# Helmet_Drop_V1.net
KiCad netlist of a schematic drawn in EAGLE
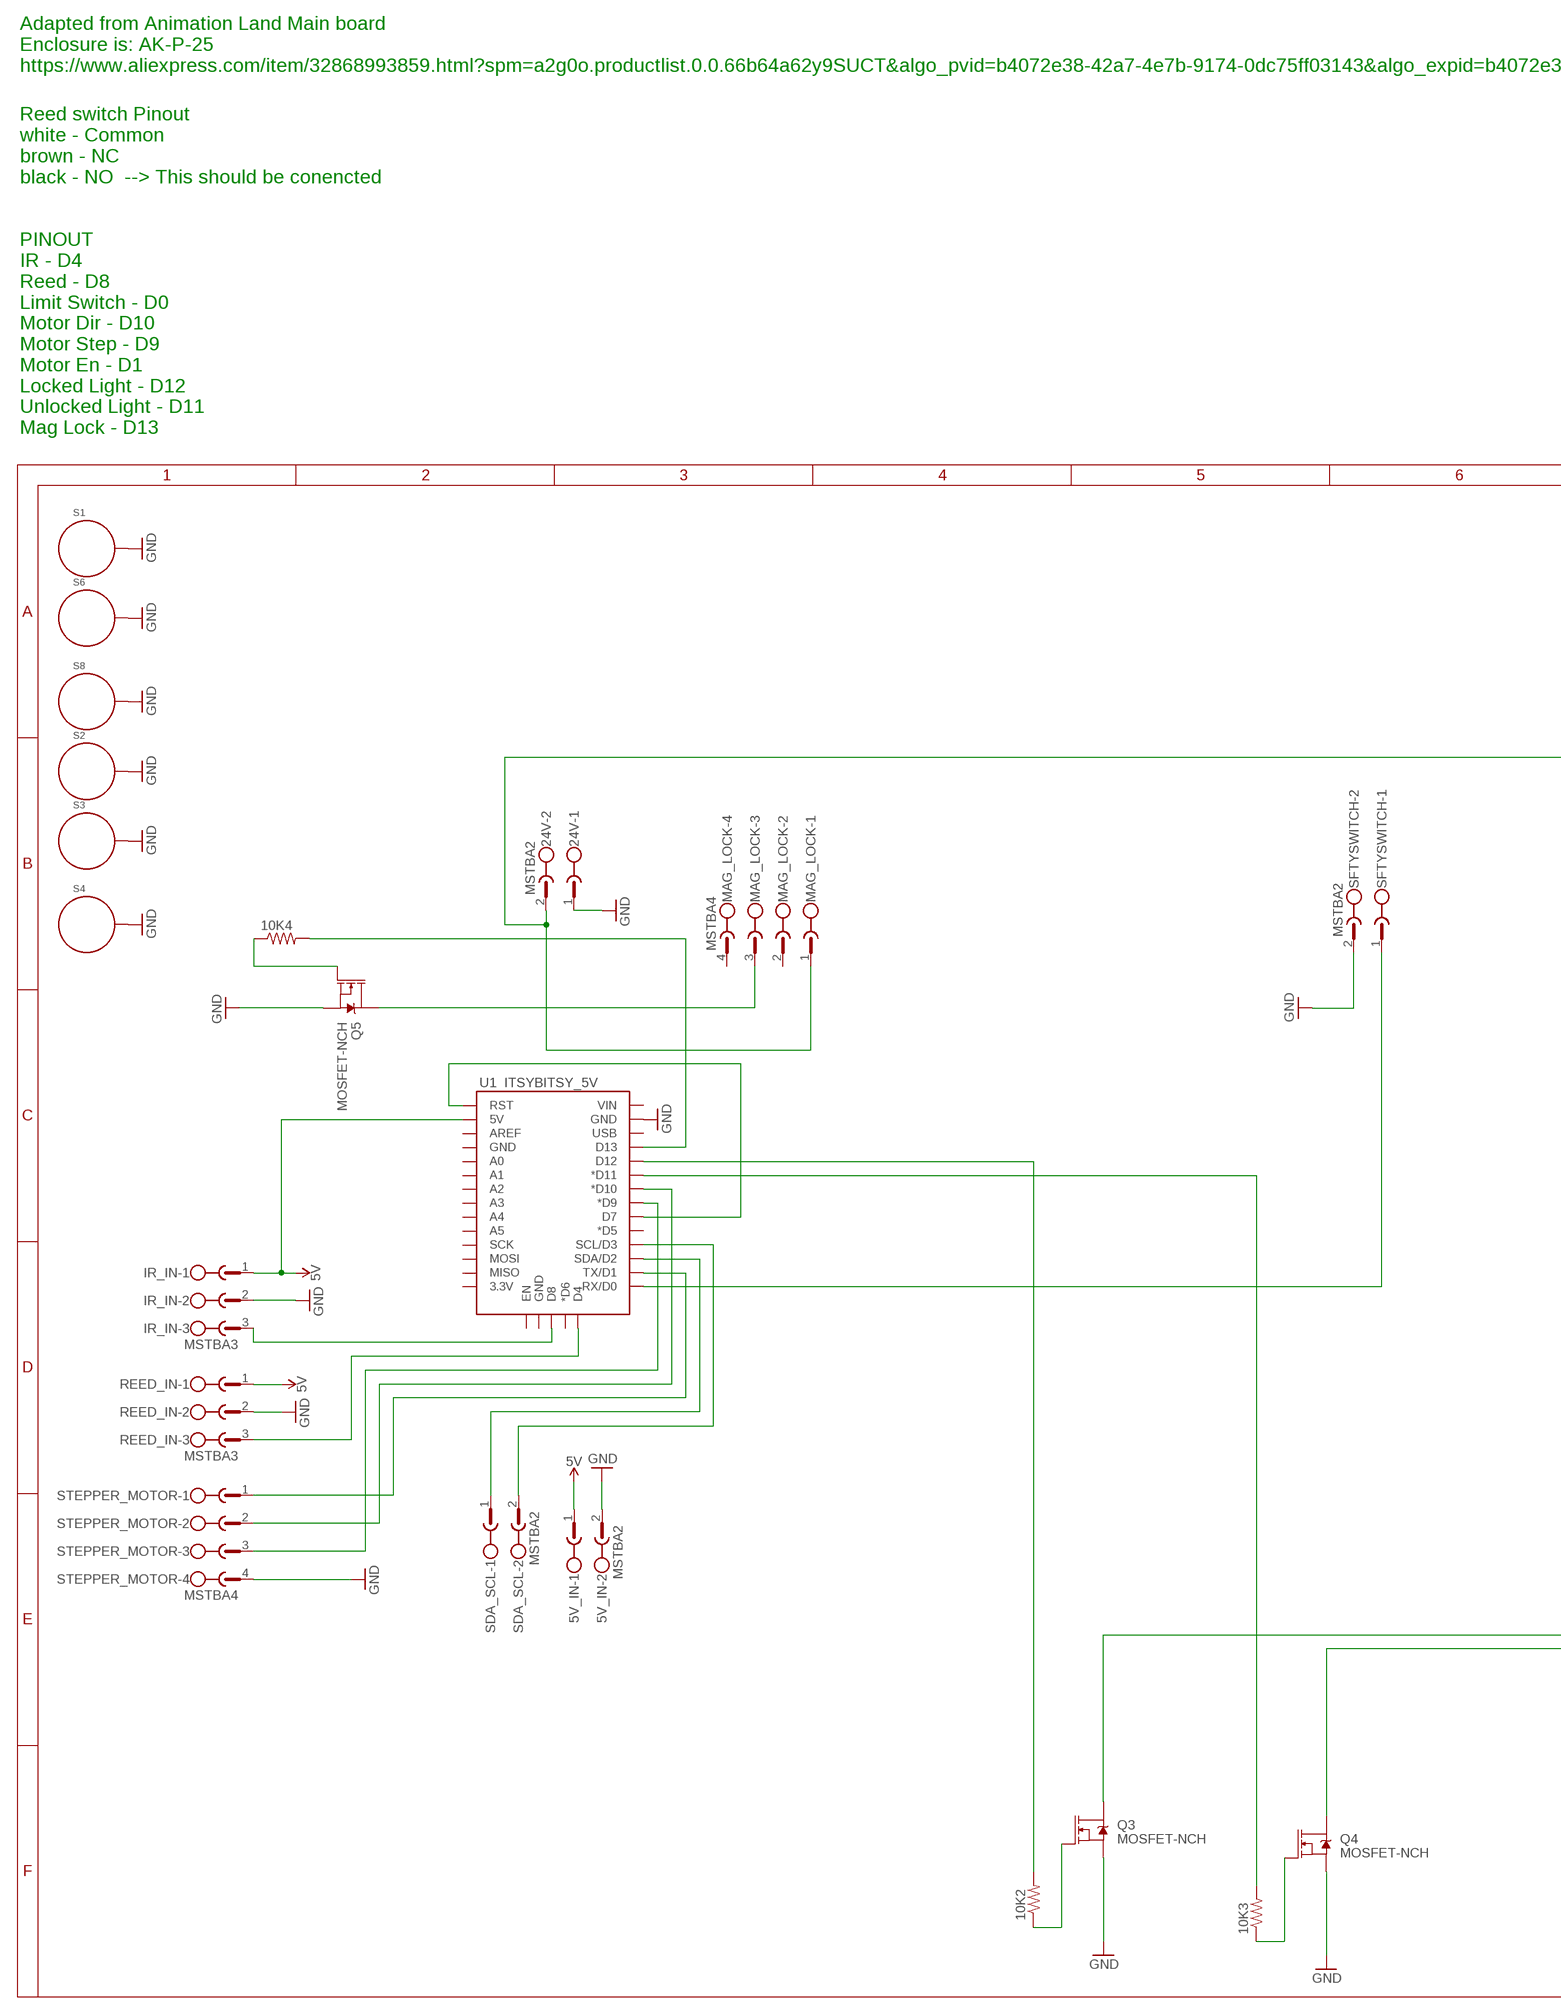
[diagram p0: schematic, sheet 1, part 1 of 2]
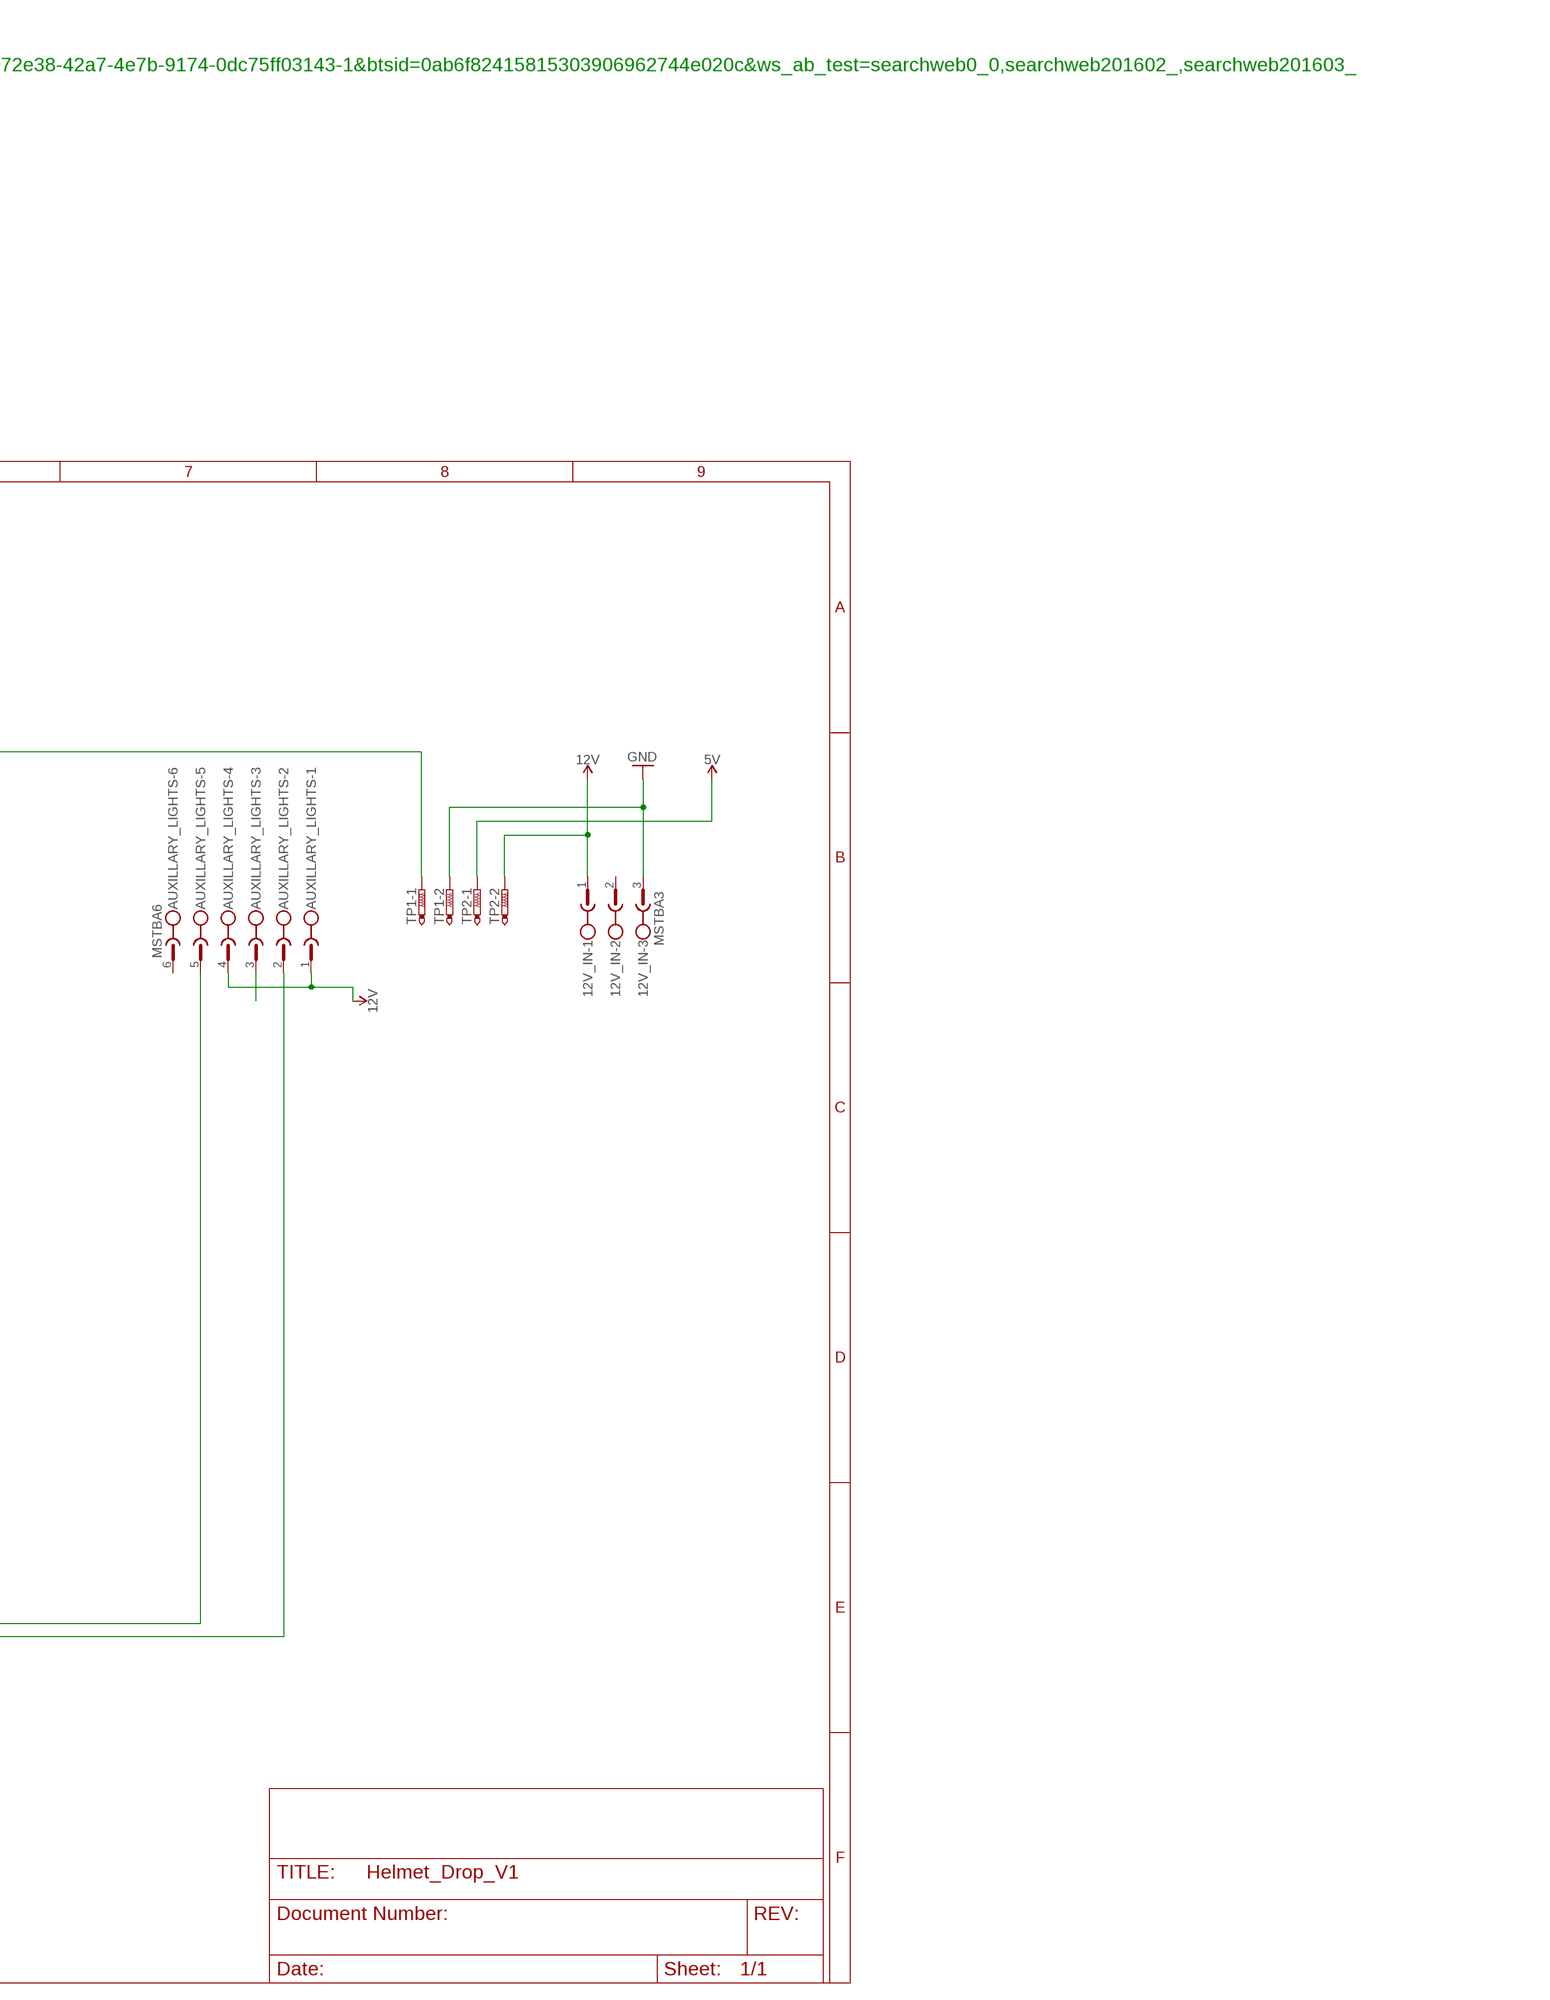
[diagram p1: schematic, sheet 1, part 2 of 2]

(export (version "E")
  (design (tool "Eeschema 10.0.6"))
  (components
    (comp (ref "5V_IN")
      (value "MSTBA2")
      (footprint "eagle-import:MSTBA2")
      (fields (field (name "MF") "FARNELL") (field (name "MPN") "1757242"))
      (libsource (lib "eagle-import") (part "MSTBA2"))
    )
    (comp (ref "10K2")
      (value "R-US_M0805")
      (footprint "eagle-import:M0805")
      (libsource (lib "eagle-import") (part "R-US_M0805"))
    )
    (comp (ref "10K3")
      (value "R-US_M0805")
      (footprint "eagle-import:M0805")
      (libsource (lib "eagle-import") (part "R-US_M0805"))
    )
    (comp (ref "10K4")
      (value "R-US_M0805")
      (footprint "eagle-import:M0805")
      (libsource (lib "eagle-import") (part "R-US_M0805"))
    )
    (comp (ref "12V_IN")
      (value "MSTBA3")
      (footprint "eagle-import:MSTBA3")
      (fields (field (name "MF") "FARNELL") (field (name "MPN") "1757255"))
      (libsource (lib "eagle-import") (part "MSTBA3"))
    )
    (comp (ref "24V")
      (value "MSTBA2")
      (footprint "eagle-import:MSTBA2")
      (fields (field (name "MF") "FARNELL") (field (name "MPN") "1757242"))
      (libsource (lib "eagle-import") (part "MSTBA2"))
    )
    (comp (ref "AUXILLARY_LIGHTS")
      (value "MSTBA6")
      (footprint "eagle-import:MSTBA6")
      (fields (field (name "MF") "FARNELL") (field (name "MPN") "1757284"))
      (libsource (lib "eagle-import") (part "MSTBA6"))
    )
    (comp (ref "IR_IN")
      (value "MSTBA3")
      (footprint "eagle-import:MSTBA3")
      (fields (field (name "MF") "FARNELL") (field (name "MPN") "1757255"))
      (libsource (lib "eagle-import") (part "MSTBA3"))
    )
    (comp (ref "MAG_LOCK")
      (value "MSTBA4")
      (footprint "eagle-import:MSTBA4")
      (fields (field (name "MF") "FARNELL") (field (name "MPN") "1757268"))
      (libsource (lib "eagle-import") (part "MSTBA4"))
    )
    (comp (ref "Q3")
      (value "MOSFET-NCH")
      (footprint "eagle-import:SO-8_POWER_PAK")
      (libsource (lib "eagle-import") (part "MOSFET-NCH"))
    )
    (comp (ref "Q4")
      (value "MOSFET-NCH")
      (footprint "eagle-import:SO-8_POWER_PAK")
      (libsource (lib "eagle-import") (part "MOSFET-NCH"))
    )
    (comp (ref "Q5")
      (value "MOSFET-NCH")
      (footprint "eagle-import:SO-8_POWER_PAK")
      (libsource (lib "eagle-import") (part "MOSFET-NCH"))
    )
    (comp (ref "REED_IN")
      (value "MSTBA3")
      (footprint "eagle-import:MSTBA3")
      (fields (field (name "MF") "FARNELL") (field (name "MPN") "1757255"))
      (libsource (lib "eagle-import") (part "MSTBA3"))
    )
    (comp (ref "S1")
      (value "STANDOFF_ELECTRICAL5-32")
      (footprint "eagle-import:STANDOFF_ELECTRICAL_5_32")
      (libsource (lib "eagle-import") (part "STANDOFF_ELECTRICAL5-32"))
    )
    (comp (ref "S2")
      (value "STANDOFF_ELECTRICAL5-32")
      (footprint "eagle-import:STANDOFF_ELECTRICAL_5_32")
      (libsource (lib "eagle-import") (part "STANDOFF_ELECTRICAL5-32"))
    )
    (comp (ref "S3")
      (value "STANDOFF_ELECTRICAL5-32")
      (footprint "eagle-import:STANDOFF_ELECTRICAL_5_32")
      (libsource (lib "eagle-import") (part "STANDOFF_ELECTRICAL5-32"))
    )
    (comp (ref "S4")
      (value "STANDOFF_ELECTRICAL5-32")
      (footprint "eagle-import:STANDOFF_ELECTRICAL_5_32")
      (libsource (lib "eagle-import") (part "STANDOFF_ELECTRICAL5-32"))
    )
    (comp (ref "S6")
      (value "STANDOFF_ELECTRICAL5-32")
      (footprint "eagle-import:STANDOFF_ELECTRICAL_5_32")
      (libsource (lib "eagle-import") (part "STANDOFF_ELECTRICAL5-32"))
    )
    (comp (ref "S8")
      (value "STANDOFF_ELECTRICAL5-32")
      (footprint "eagle-import:STANDOFF_ELECTRICAL_5_32")
      (libsource (lib "eagle-import") (part "STANDOFF_ELECTRICAL5-32"))
    )
    (comp (ref "SDA_SCL")
      (value "MSTBA2")
      (footprint "eagle-import:MSTBA2")
      (fields (field (name "MF") "FARNELL") (field (name "MPN") "1757242"))
      (libsource (lib "eagle-import") (part "MSTBA2"))
    )
    (comp (ref "SFTYSWITCH")
      (value "MSTBA2")
      (footprint "eagle-import:MSTBA2")
      (fields (field (name "MF") "FARNELL") (field (name "MPN") "1757242"))
      (libsource (lib "eagle-import") (part "MSTBA2"))
    )
    (comp (ref "STEPPER_MOTOR")
      (value "MSTBA4")
      (footprint "eagle-import:MSTBA4")
      (fields (field (name "MF") "FARNELL") (field (name "MPN") "1757268"))
      (libsource (lib "eagle-import") (part "MSTBA4"))
    )
    (comp (ref "TP1")
      (value "PTR2")
      (footprint "eagle-import:P2-38-17")
      (libsource (lib "eagle-import") (part "PTR2"))
    )
    (comp (ref "TP2")
      (value "PTR2")
      (footprint "eagle-import:P2-38-17")
      (libsource (lib "eagle-import") (part "PTR2"))
    )
    (comp (ref "U1")
      (value "ITSYBITSY_5V")
      (footprint "eagle-import:ADAFRUIT_LENOARDO")
      (libsource (lib "eagle-import") (part "ITSYBITSY_5V"))
    )
  )
  (nets
    (net (code "1") (name "5V") (class "Default")
      (node (ref "5V_IN") (pin "1") (pinfunction "1_1") (pintype "passive"))
      (node (ref "IR_IN") (pin "1") (pinfunction "1_1") (pintype "passive"))
      (node (ref "REED_IN") (pin "1") (pinfunction "1_1") (pintype "passive"))
      (node (ref "TP2") (pin "TP-1") (pinfunction "TP_TP-1") (pintype "input"))
      (node (ref "U1") (pin "5V") (pinfunction "5V_5V") (pintype "bidirectional"))
    )
    (net (code "2") (name "12V") (class "Default")
      (node (ref "12V_IN") (pin "1") (pinfunction "1_1") (pintype "passive"))
      (node (ref "AUXILLARY_LIGHTS") (pin "1") (pinfunction "1_1") (pintype "passive"))
      (node (ref "AUXILLARY_LIGHTS") (pin "4") (pinfunction "1_4") (pintype "passive"))
      (node (ref "TP2") (pin "TP-2") (pinfunction "TP_TP-2") (pintype "input"))
    )
    (net (code "3") (name "GND") (class "Default")
      (node (ref "12V_IN") (pin "3") (pinfunction "1_3") (pintype "passive"))
      (node (ref "24V") (pin "1") (pinfunction "1_1") (pintype "passive"))
      (node (ref "5V_IN") (pin "2") (pinfunction "1_2") (pintype "passive"))
      (node (ref "IR_IN") (pin "2") (pinfunction "1_2") (pintype "passive"))
      (node (ref "Q3") (pin "S") (pinfunction "S_S") (pintype "bidirectional"))
      (node (ref "Q4") (pin "S") (pinfunction "S_S") (pintype "bidirectional"))
      (node (ref "Q5") (pin "S") (pinfunction "S_S") (pintype "bidirectional"))
      (node (ref "REED_IN") (pin "2") (pinfunction "1_2") (pintype "passive"))
      (node (ref "S1") (pin "P1") (pinfunction "P$1_P1") (pintype "bidirectional"))
      (node (ref "S2") (pin "P1") (pinfunction "P$1_P1") (pintype "bidirectional"))
      (node (ref "S3") (pin "P1") (pinfunction "P$1_P1") (pintype "bidirectional"))
      (node (ref "S4") (pin "P1") (pinfunction "P$1_P1") (pintype "bidirectional"))
      (node (ref "S6") (pin "P1") (pinfunction "P$1_P1") (pintype "bidirectional"))
      (node (ref "S8") (pin "P1") (pinfunction "P$1_P1") (pintype "bidirectional"))
      (node (ref "SFTYSWITCH") (pin "2") (pinfunction "1_2") (pintype "passive"))
      (node (ref "STEPPER_MOTOR") (pin "4") (pinfunction "1_4") (pintype "passive"))
      (node (ref "TP1") (pin "TP-2") (pinfunction "TP_TP-2") (pintype "input"))
      (node (ref "U1") (pin "GND@2") (pinfunction "GND_GND@2") (pintype "bidirectional"))
    )
    (net (code "4") (name "Net-(10K2-Pad1)") (class "Default")
      (node (ref "10K2") (pin "1") (pinfunction "1_1") (pintype "passive"))
      (node (ref "Q3") (pin "G") (pinfunction "G_G") (pintype "bidirectional"))
    )
    (net (code "5") (name "Net-(10K2-Pad2)") (class "Default")
      (node (ref "10K2") (pin "2") (pinfunction "2_2") (pintype "passive"))
      (node (ref "U1") (pin "D12") (pinfunction "D12_D12") (pintype "bidirectional"))
    )
    (net (code "6") (name "Net-(10K3-Pad1)") (class "Default")
      (node (ref "10K3") (pin "1") (pinfunction "1_1") (pintype "passive"))
      (node (ref "Q4") (pin "G") (pinfunction "G_G") (pintype "bidirectional"))
    )
    (net (code "7") (name "Net-(10K4-Pad1)") (class "Default")
      (node (ref "10K4") (pin "1") (pinfunction "1_1") (pintype "passive"))
      (node (ref "Q5") (pin "G") (pinfunction "G_G") (pintype "bidirectional"))
    )
    (net (code "8") (name "Net-(10K4-Pad2)") (class "Default")
      (node (ref "10K4") (pin "2") (pinfunction "2_2") (pintype "passive"))
      (node (ref "U1") (pin "D13") (pinfunction "D13_D13") (pintype "bidirectional"))
    )
    (net (code "9") (name "Net-(24VB-1)") (class "Default")
      (node (ref "24V") (pin "2") (pinfunction "1_2") (pintype "passive"))
      (node (ref "MAG_LOCK") (pin "1") (pinfunction "1_1") (pintype "passive"))
      (node (ref "TP1") (pin "TP-1") (pinfunction "TP_TP-1") (pintype "input"))
    )
    (net (code "10") (name "Net-(AUXILLARY_LIGHTSB-1)") (class "Default")
      (node (ref "AUXILLARY_LIGHTS") (pin "2") (pinfunction "1_2") (pintype "passive"))
      (node (ref "Q4") (pin "D1") (pinfunction "D_D1") (pintype "bidirectional"))
    )
    (net (code "11") (name "Net-(AUXILLARY_LIGHTSE-1)") (class "Default")
      (node (ref "AUXILLARY_LIGHTS") (pin "5") (pinfunction "1_5") (pintype "passive"))
      (node (ref "Q3") (pin "D1") (pinfunction "D_D1") (pintype "bidirectional"))
    )
    (net (code "12") (name "Net-(IR_INC-1)") (class "Default")
      (node (ref "IR_IN") (pin "3") (pinfunction "1_3") (pintype "passive"))
      (node (ref "U1") (pin "D8") (pinfunction "D8_D8") (pintype "bidirectional"))
    )
    (net (code "13") (name "Net-(MAG_LOCKC-1)") (class "Default")
      (node (ref "MAG_LOCK") (pin "3") (pinfunction "1_3") (pintype "passive"))
      (node (ref "Q5") (pin "D1") (pinfunction "D_D1") (pintype "bidirectional"))
    )
    (net (code "14") (name "Net-(REED_INC-1)") (class "Default")
      (node (ref "REED_IN") (pin "3") (pinfunction "1_3") (pintype "passive"))
      (node (ref "U1") (pin "D4") (pinfunction "D4_D4") (pintype "bidirectional"))
    )
    (net (code "15") (name "Net-(SDA_SCLB-1)") (class "Default")
      (node (ref "SDA_SCL") (pin "2") (pinfunction "1_2") (pintype "passive"))
      (node (ref "U1") (pin "SCL") (pinfunction "SCL/D3_SCL") (pintype "bidirectional"))
    )
    (net (code "16") (name "Net-(STEPPER_MOTORB-1)") (class "Default")
      (node (ref "STEPPER_MOTOR") (pin "2") (pinfunction "1_2") (pintype "passive"))
      (node (ref "U1") (pin "D10") (pinfunction "*D10_D10") (pintype "bidirectional"))
    )
    (net (code "17") (name "Net-(STEPPER_MOTORC-1)") (class "Default")
      (node (ref "STEPPER_MOTOR") (pin "3") (pinfunction "1_3") (pintype "passive"))
      (node (ref "U1") (pin "D9") (pinfunction "*D9_D9") (pintype "bidirectional"))
    )
    (net (code "18") (name "Net-(U1-*D11)") (class "Default")
      (node (ref "10K3") (pin "2") (pinfunction "2_2") (pintype "passive"))
      (node (ref "U1") (pin "D11") (pinfunction "*D11_D11") (pintype "bidirectional"))
    )
    (net (code "19") (name "Net-(U1-RST)") (class "Default")
      (node (ref "U1") (pin "D7") (pinfunction "D7_D7") (pintype "bidirectional"))
      (node (ref "U1") (pin "RES") (pinfunction "RST_RES") (pintype "bidirectional"))
    )
    (net (code "20") (name "Net-(U1-RX{slash}D0)") (class "Default")
      (node (ref "SFTYSWITCH") (pin "1") (pinfunction "1_1") (pintype "passive"))
      (node (ref "U1") (pin "RX") (pinfunction "RX/D0_RX") (pintype "bidirectional"))
    )
    (net (code "21") (name "Net-(U1-SDA{slash}D2)") (class "Default")
      (node (ref "SDA_SCL") (pin "1") (pinfunction "1_1") (pintype "passive"))
      (node (ref "U1") (pin "SDA") (pinfunction "SDA/D2_SDA") (pintype "bidirectional"))
    )
    (net (code "22") (name "Net-(U1-TX{slash}D1)") (class "Default")
      (node (ref "STEPPER_MOTOR") (pin "1") (pinfunction "1_1") (pintype "passive"))
      (node (ref "U1") (pin "TX") (pinfunction "TX/D1_TX") (pintype "bidirectional"))
    )
    (net (code "23") (name "unconnected-(12V_INB-1-Pad2)") (class "Default")
      (node (ref "12V_IN") (pin "2") (pinfunction "1_2") (pintype "passive"))
    )
    (net (code "24") (name "unconnected-(AUXILLARY_LIGHTSC-1-Pad3)") (class "Default")
      (node (ref "AUXILLARY_LIGHTS") (pin "3") (pinfunction "1_3") (pintype "passive"))
    )
    (net (code "25") (name "unconnected-(AUXILLARY_LIGHTSF-1-Pad6)") (class "Default")
      (node (ref "AUXILLARY_LIGHTS") (pin "6") (pinfunction "1_6") (pintype "passive"))
    )
    (net (code "26") (name "unconnected-(MAG_LOCKB-1-Pad2)") (class "Default")
      (node (ref "MAG_LOCK") (pin "2") (pinfunction "1_2") (pintype "passive"))
    )
    (net (code "27") (name "unconnected-(MAG_LOCKD-1-Pad4)") (class "Default")
      (node (ref "MAG_LOCK") (pin "4") (pinfunction "1_4") (pintype "passive"))
    )
    (net (code "28") (name "unconnected-(U1-*D5-PadD5)") (class "Default")
      (node (ref "U1") (pin "D5") (pinfunction "*D5_D5") (pintype "bidirectional"))
    )
    (net (code "29") (name "unconnected-(U1-*D6-PadD6)") (class "Default")
      (node (ref "U1") (pin "D6") (pinfunction "*D6_D6") (pintype "bidirectional"))
    )
    (net (code "30") (name "unconnected-(U1-3.3V-Pad3V)") (class "Default")
      (node (ref "U1") (pin "3V") (pinfunction "3.3V_3V") (pintype "bidirectional"))
    )
    (net (code "31") (name "unconnected-(U1-GND-PadGND@0)") (class "Default")
      (node (ref "U1") (pin "GND@0") (pinfunction "GND_GND@0") (pintype "bidirectional"))
    )
    (net (code "32") (name "unconnected-(U1-GND-PadGND@1)") (class "Default")
      (node (ref "U1") (pin "GND@1") (pinfunction "GND_GND@1") (pintype "bidirectional"))
    )
    (net (code "33") (name "unconnected-(U1-PadA0)") (class "Default")
      (node (ref "U1") (pin "A0") (pinfunction "A0_A0") (pintype "bidirectional"))
    )
    (net (code "34") (name "unconnected-(U1-PadA1)") (class "Default")
      (node (ref "U1") (pin "A1") (pinfunction "A1_A1") (pintype "bidirectional"))
    )
    (net (code "35") (name "unconnected-(U1-PadA2)") (class "Default")
      (node (ref "U1") (pin "A2") (pinfunction "A2_A2") (pintype "bidirectional"))
    )
    (net (code "36") (name "unconnected-(U1-PadA3)") (class "Default")
      (node (ref "U1") (pin "A3") (pinfunction "A3_A3") (pintype "bidirectional"))
    )
    (net (code "37") (name "unconnected-(U1-PadA4)") (class "Default")
      (node (ref "U1") (pin "A4") (pinfunction "A4_A4") (pintype "bidirectional"))
    )
    (net (code "38") (name "unconnected-(U1-PadA5)") (class "Default")
      (node (ref "U1") (pin "A5") (pinfunction "A5_A5") (pintype "bidirectional"))
    )
    (net (code "39") (name "unconnected-(U1-PadAREF)") (class "Default")
      (node (ref "U1") (pin "AREF") (pinfunction "AREF_AREF") (pintype "bidirectional"))
    )
    (net (code "40") (name "unconnected-(U1-PadEN)") (class "Default")
      (node (ref "U1") (pin "EN") (pinfunction "EN_EN") (pintype "bidirectional"))
    )
    (net (code "41") (name "unconnected-(U1-PadMISO)") (class "Default")
      (node (ref "U1") (pin "MISO") (pinfunction "MISO_MISO") (pintype "bidirectional"))
    )
    (net (code "42") (name "unconnected-(U1-PadMOSI)") (class "Default")
      (node (ref "U1") (pin "MOSI") (pinfunction "MOSI_MOSI") (pintype "bidirectional"))
    )
    (net (code "43") (name "unconnected-(U1-PadSCK)") (class "Default")
      (node (ref "U1") (pin "SCK") (pinfunction "SCK_SCK") (pintype "bidirectional"))
    )
    (net (code "44") (name "unconnected-(U1-PadUSB)") (class "Default")
      (node (ref "U1") (pin "USB") (pinfunction "USB_USB") (pintype "bidirectional"))
    )
    (net (code "45") (name "unconnected-(U1-PadVIN)") (class "Default")
      (node (ref "U1") (pin "VIN") (pinfunction "VIN_VIN") (pintype "bidirectional"))
    )
  )
)
